# tuch-tara2.net
KiCad netlist of a schematic drawn in Altium Designer
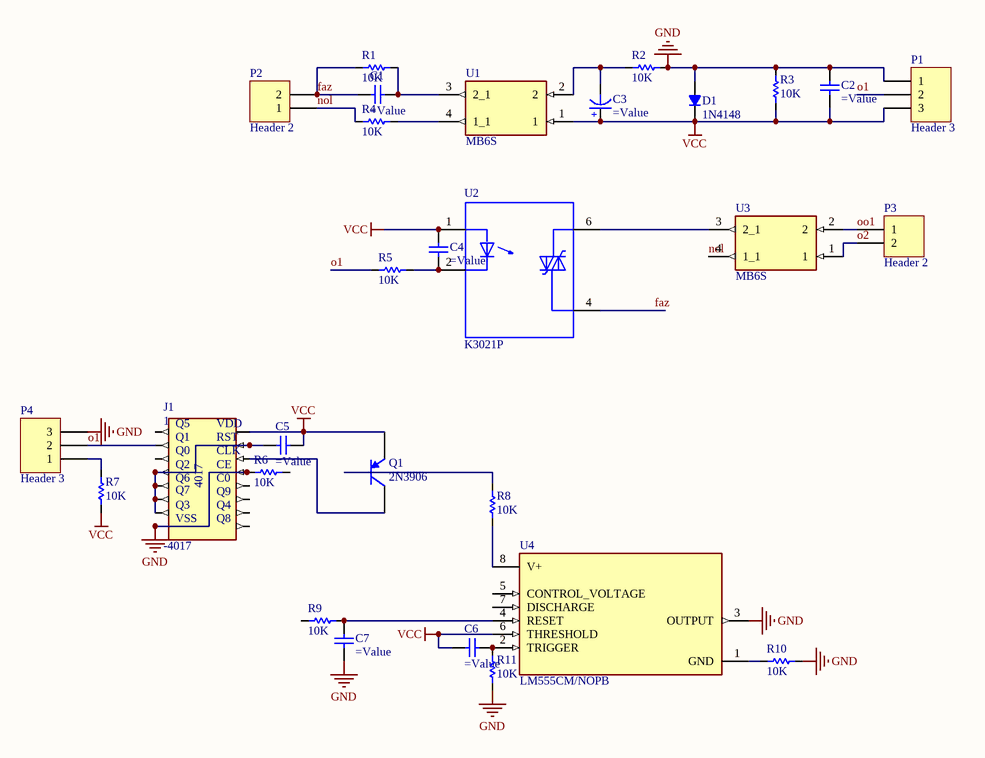
[diagram p0: tuch-tara2.SchDoc]

(export (version "E")
  (design (tool "Eeschema 10.0.6"))
  (components
    (comp (ref "C1")
      (value "~")
      (footprint "CAP-30")
      (description "Capacitor")
      (libsource (lib "AltiumLib1") (part "Capacitor"))
    )
    (comp (ref "C2")
      (value "~")
      (footprint "CAP 1206")
      (description "Capacitor")
      (libsource (lib "AltiumLib1") (part "Capacitor"))
    )
    (comp (ref "C3")
      (value "~")
      (footprint "ELEC-CAP-RAD10-20")
      (description "Electrolytic Capacitor")
      (libsource (lib "AltiumLib1") (part "Capacitor Electrolytic"))
    )
    (comp (ref "C4")
      (value "~")
      (footprint "CAP 1206")
      (description "Capacitor")
      (libsource (lib "AltiumLib1") (part "Capacitor"))
    )
    (comp (ref "C5")
      (value "~")
      (footprint "CAP 1206")
      (description "Capacitor")
      (libsource (lib "AltiumLib1") (part "Capacitor"))
    )
    (comp (ref "C6")
      (value "~")
      (footprint "CAP 1206")
      (description "Capacitor")
      (libsource (lib "AltiumLib1") (part "Capacitor"))
    )
    (comp (ref "C7")
      (value "~")
      (footprint "CAP 1206")
      (description "Capacitor")
      (libsource (lib "AltiumLib1") (part "Capacitor"))
    )
    (comp (ref "D1")
      (value "MODEL")
      (footprint "DO-41")
      (description "Diode")
      (fields (field (name "MODEL") "1N4148"))
      (libsource (lib "AltiumLib1") (part "Diode"))
    )
    (comp (ref "J1")
      (value "-4017")
      (footprint "SOIC127P600X175-16N")
      (description "10000pF Â±1% 25V Ceramic Capacitor C0G, NP0 0603 (1608 Metric)")
      (fields (field (name "MF") "Heyco") (field (name "MP") "4017"))
      (libsource (lib "-4017") (part "-4017"))
    )
    (comp (ref "P1")
      (value "Header 3")
      (footprint "HDR1X3")
      (description "Header, 3-Pin")
      (fields (field (name "PUBLISHER") "Altium Limited"))
      (libsource (lib "") (part "Header 3_1"))
    )
    (comp (ref "P2")
      (value "Header 2")
      (footprint "HDR1X2")
      (description "Header, 2-Pin")
      (fields (field (name "PUBLISHER") "Altium Limited"))
      (libsource (lib "") (part "Header 2_1"))
    )
    (comp (ref "P3")
      (value "Header 2")
      (footprint "HDR1X2")
      (description "Header, 2-Pin")
      (fields (field (name "PUBLISHER") "Altium Limited"))
      (libsource (lib "Miscellaneous Connectors") (part "Header 2"))
    )
    (comp (ref "P4")
      (value "Header 3")
      (footprint "HDR1X3")
      (description "Header, 3-Pin")
      (fields (field (name "PUBLISHER") "Altium Limited"))
      (libsource (lib "Miscellaneous Connectors") (part "Header 3"))
    )
    (comp (ref "Q1")
      (value "2N3906")
      (footprint "MMBT3904-TP:SOT23-3")
      (description "PNP General Purpose Amplifier")
      (fields (field (name "PUBLISHER") "Altium Limited"))
      (libsource (lib "Miscellaneous Devices") (part "2N3906"))
    )
    (comp (ref "R1")
      (value "10K")
      (footprint "RES 1206 (3216X08L)")
      (description "Resistor")
      (fields (field (name "TOLERANCE") "5%") (field (name "POWER") "1/4 W"))
      (libsource (lib "AltiumLib1") (part "Resistor"))
    )
    (comp (ref "R2")
      (value "10K")
      (footprint "RES 1206 (3216X08L)")
      (description "Resistor")
      (fields (field (name "TOLERANCE") "5%") (field (name "POWER") "1/4 W"))
      (libsource (lib "AltiumLib1") (part "Resistor"))
    )
    (comp (ref "R3")
      (value "10K")
      (footprint "RES 1206 (3216X08L)")
      (description "Resistor")
      (fields (field (name "TOLERANCE") "5%") (field (name "POWER") "1/4 W"))
      (libsource (lib "AltiumLib1") (part "Resistor"))
    )
    (comp (ref "R4")
      (value "10K")
      (footprint "RES 2512 (6331X07L)")
      (description "Resistor")
      (fields (field (name "TOLERANCE") "5%") (field (name "POWER") "1/4 W"))
      (libsource (lib "AltiumLib1") (part "Resistor"))
    )
    (comp (ref "R5")
      (value "10K")
      (footprint "RES 1206 (3216X08L)")
      (description "Resistor")
      (fields (field (name "TOLERANCE") "5%") (field (name "POWER") "1/4 W"))
      (libsource (lib "AltiumLib1") (part "Resistor"))
    )
    (comp (ref "R6")
      (value "10K")
      (footprint "RES 1206 (3216X08L)")
      (description "Resistor")
      (fields (field (name "TOLERANCE") "5%") (field (name "POWER") "1/4 W"))
      (libsource (lib "AltiumLib1") (part "Resistor"))
    )
    (comp (ref "R7")
      (value "10K")
      (footprint "Res-(1/4)")
      (description "Resistor")
      (fields (field (name "TOLERANCE") "5%") (field (name "POWER") "1/4 W"))
      (libsource (lib "AltiumLib1") (part "Resistor"))
    )
    (comp (ref "R8")
      (value "10K")
      (footprint "RES 1206 (3216X08L)")
      (description "Resistor")
      (fields (field (name "TOLERANCE") "5%") (field (name "POWER") "1/4 W"))
      (libsource (lib "AltiumLib1") (part "Resistor"))
    )
    (comp (ref "R9")
      (value "10K")
      (footprint "RES 1206 (3216X08L)")
      (description "Resistor")
      (fields (field (name "TOLERANCE") "5%") (field (name "POWER") "1/4 W"))
      (libsource (lib "AltiumLib1") (part "Resistor"))
    )
    (comp (ref "R10")
      (value "10K")
      (footprint "RES 1206 (3216X08L)")
      (description "Resistor")
      (fields (field (name "TOLERANCE") "5%") (field (name "POWER") "1/4 W"))
      (libsource (lib "AltiumLib1") (part "Resistor"))
    )
    (comp (ref "R11")
      (value "10K")
      (footprint "RES 1206 (3216X08L)")
      (description "Resistor")
      (fields (field (name "TOLERANCE") "5%") (field (name "POWER") "1/4 W"))
      (libsource (lib "AltiumLib1") (part "Resistor"))
    )
    (comp (ref "U1")
      (value "MB6S")
      (footprint "SOIC245P670X270-4N")
      (description "Bridge Rectifier Single Phase Standard 600V Surface Mount 4-SOIC")
      (fields (field (name "MF") "ON Semiconductor") (field (name "DIGI-KEY_PART_NUMBER") "MB6SCT-ND"))
      (libsource (lib "MB6S") (part "MB6S"))
    )
    (comp (ref "U2")
      (value "K3021P")
      (footprint "DIP762W50P254L730H410Q6")
      (description "Optoisolator Triac Output 5300Vrms 1 Channel 6-DIP")
      (fields (field (name "MF") "Vishay Semiconductor"))
      (libsource (lib "K3021P") (part "K3021P"))
    )
    (comp (ref "U3")
      (value "MB6S")
      (footprint "SOIC245P670X270-4N")
      (description "Bridge Rectifier Single Phase Standard 600V Surface Mount 4-SOIC")
      (fields (field (name "MF") "ON Semiconductor") (field (name "DIGI-KEY_PART_NUMBER") "MB6SCT-ND"))
      (libsource (lib "MB6S") (part "MB6S"))
    )
    (comp (ref "U4")
      (value "LM555CM/NOPB")
      (footprint "SOIC127P599X175-8N")
      (description "Highly Stable 555 Timer 8-SOIC 0 to 70")
      (libsource (lib "LM555CM_NOPB") (part "LM555CM/NOPB"))
    )
  )
  (nets
    (net (code "1") (name "/faz") (class "Default")
      (node (ref "C1") (pin "1") (pinfunction "+_1") (pintype "passive"))
      (node (ref "P2") (pin "2") (pinfunction "2_2") (pintype "passive"))
      (node (ref "R1") (pin "2") (pinfunction "2_2") (pintype "passive"))
      (node (ref "U2") (pin "4") (pinfunction "MT1_4") (pintype "passive"))
    )
    (net (code "2") (name "/nol") (class "Default")
      (node (ref "P2") (pin "1") (pinfunction "1_1") (pintype "passive"))
      (node (ref "R4") (pin "2") (pinfunction "2_2") (pintype "passive"))
      (node (ref "U3") (pin "4") (pinfunction "1_1_4") (pintype "output"))
    )
    (net (code "3") (name "/o1") (class "Default")
      (node (ref "J1") (pin "2") (pinfunction "Q1_2") (pintype "output"))
      (node (ref "P1") (pin "2") (pinfunction "2_2") (pintype "passive"))
      (node (ref "P4") (pin "2") (pinfunction "2_2") (pintype "passive"))
      (node (ref "R5") (pin "1") (pinfunction "1_1") (pintype "passive"))
    )
    (net (code "4") (name "/o2") (class "Default")
      (node (ref "P3") (pin "2") (pinfunction "2_2") (pintype "passive"))
      (node (ref "U3") (pin "1") (pinfunction "1_1") (pintype "input"))
    )
    (net (code "5") (name "/oo1") (class "Default")
      (node (ref "P3") (pin "1") (pinfunction "1_1") (pintype "passive"))
      (node (ref "U3") (pin "2") (pinfunction "2_2") (pintype "input"))
    )
    (net (code "6") (name "GND") (class "Default")
      (node (ref "C2") (pin "2") (pinfunction "-_2") (pintype "passive"))
      (node (ref "C7") (pin "2") (pinfunction "-_2") (pintype "passive"))
      (node (ref "D1") (pin "1") (pinfunction "A_1") (pintype "passive"))
      (node (ref "J1") (pin "13") (pinfunction "CE_13") (pintype "input"))
      (node (ref "J1") (pin "8") (pinfunction "VSS_8") (pintype "power_in"))
      (node (ref "P1") (pin "1") (pinfunction "1_1") (pintype "passive"))
      (node (ref "P4") (pin "3") (pinfunction "3_3") (pintype "passive"))
      (node (ref "R10") (pin "2") (pinfunction "2_2") (pintype "passive"))
      (node (ref "R11") (pin "1") (pinfunction "1_1") (pintype "passive"))
      (node (ref "R2") (pin "2") (pinfunction "2_2") (pintype "passive"))
      (node (ref "R3") (pin "2") (pinfunction "2_2") (pintype "passive"))
      (node (ref "R6") (pin "1") (pinfunction "1_1") (pintype "passive"))
      (node (ref "U4") (pin "3") (pinfunction "OUTPUT_3") (pintype "output"))
    )
    (net (code "7") (name "Net-(C1--)") (class "Default")
      (node (ref "C1") (pin "2") (pinfunction "-_2") (pintype "passive"))
      (node (ref "R1") (pin "1") (pinfunction "1_1") (pintype "passive"))
      (node (ref "U1") (pin "3") (pinfunction "2_1_3") (pintype "output"))
    )
    (net (code "8") (name "Net-(C3--)") (class "Default")
      (node (ref "C3") (pin "1") (pinfunction "-_1") (pintype "passive"))
      (node (ref "R2") (pin "1") (pinfunction "1_1") (pintype "passive"))
      (node (ref "U1") (pin "2") (pinfunction "2_2") (pintype "input"))
    )
    (net (code "9") (name "Net-(C4-+)") (class "Default")
      (node (ref "C4") (pin "1") (pinfunction "+_1") (pintype "passive"))
      (node (ref "R5") (pin "2") (pinfunction "2_2") (pintype "passive"))
      (node (ref "U2") (pin "2") (pinfunction "C_2") (pintype "passive"))
    )
    (net (code "10") (name "Net-(C5--)") (class "Default")
      (node (ref "C5") (pin "2") (pinfunction "-_2") (pintype "passive"))
      (node (ref "J1") (pin "15") (pinfunction "RST_15") (pintype "input"))
      (node (ref "J1") (pin "4") (pinfunction "Q2_4") (pintype "output"))
      (node (ref "J1") (pin "5") (pinfunction "Q6_5") (pintype "output"))
      (node (ref "J1") (pin "6") (pinfunction "Q7_6") (pintype "output"))
      (node (ref "J1") (pin "7") (pinfunction "Q3_7") (pintype "output"))
    )
    (net (code "11") (name "Net-(C6-+)") (class "Default")
      (node (ref "C6") (pin "1") (pinfunction "+_1") (pintype "passive"))
      (node (ref "R11") (pin "2") (pinfunction "2_2") (pintype "passive"))
      (node (ref "U4") (pin "2") (pinfunction "TRIGGER_2") (pintype "input"))
    )
    (net (code "12") (name "Net-(C7-+)") (class "Default")
      (node (ref "C7") (pin "1") (pinfunction "+_1") (pintype "passive"))
      (node (ref "R9") (pin "2") (pinfunction "2_2") (pintype "passive"))
      (node (ref "U4") (pin "4") (pinfunction "RESET_4") (pintype "input"))
    )
    (net (code "13") (name "Net-(J1-CLK)") (class "Default")
      (node (ref "J1") (pin "14") (pinfunction "CLK_14") (pintype "input"))
      (node (ref "Q1") (pin "3") (pinfunction "C_3") (pintype "passive"))
    )
    (net (code "14") (name "Net-(P4-Pad1)") (class "Default")
      (node (ref "P4") (pin "1") (pinfunction "1_1") (pintype "passive"))
      (node (ref "R7") (pin "2") (pinfunction "2_2") (pintype "passive"))
    )
    (net (code "15") (name "Net-(Q1-B)") (class "Default")
      (node (ref "Q1") (pin "2") (pinfunction "B_2") (pintype "passive"))
      (node (ref "R8") (pin "2") (pinfunction "2_2") (pintype "passive"))
    )
    (net (code "16") (name "Net-(U1-1_1)") (class "Default")
      (node (ref "R4") (pin "1") (pinfunction "1_1") (pintype "passive"))
      (node (ref "U1") (pin "4") (pinfunction "1_1_4") (pintype "output"))
    )
    (net (code "17") (name "Net-(U2-MT2)") (class "Default")
      (node (ref "U2") (pin "6") (pinfunction "MT2_6") (pintype "passive"))
      (node (ref "U3") (pin "3") (pinfunction "2_1_3") (pintype "output"))
    )
    (net (code "18") (name "Net-(U4-GND)") (class "Default")
      (node (ref "R10") (pin "1") (pinfunction "1_1") (pintype "passive"))
      (node (ref "U4") (pin "1") (pinfunction "GND_1") (pintype "power_in"))
    )
    (net (code "19") (name "Net-(U4-V+)") (class "Default")
      (node (ref "R8") (pin "1") (pinfunction "1_1") (pintype "passive"))
      (node (ref "U4") (pin "8") (pinfunction "V+_8") (pintype "power_in"))
    )
    (net (code "20") (name "VCC") (class "Default")
      (node (ref "C2") (pin "1") (pinfunction "+_1") (pintype "passive"))
      (node (ref "C3") (pin "2") (pinfunction "+_2") (pintype "passive"))
      (node (ref "C4") (pin "2") (pinfunction "-_2") (pintype "passive"))
      (node (ref "C5") (pin "1") (pinfunction "+_1") (pintype "passive"))
      (node (ref "C6") (pin "2") (pinfunction "-_2") (pintype "passive"))
      (node (ref "D1") (pin "2") (pinfunction "K_2") (pintype "passive"))
      (node (ref "J1") (pin "16") (pinfunction "VDD_16") (pintype "power_in"))
      (node (ref "P1") (pin "3") (pinfunction "3_3") (pintype "passive"))
      (node (ref "Q1") (pin "1") (pinfunction "E_1") (pintype "passive"))
      (node (ref "R3") (pin "1") (pinfunction "1_1") (pintype "passive"))
      (node (ref "R7") (pin "1") (pinfunction "1_1") (pintype "passive"))
      (node (ref "U1") (pin "1") (pinfunction "1_1") (pintype "input"))
      (node (ref "U2") (pin "1") (pinfunction "A_1") (pintype "passive"))
      (node (ref "U4") (pin "6") (pinfunction "THRESHOLD_6") (pintype "input"))
    )
    (net (code "21") (name "unconnected-(J1-C0-Pad12)") (class "Default")
      (node (ref "J1") (pin "12") (pinfunction "C0_12") (pintype "output"))
    )
    (net (code "22") (name "unconnected-(J1-Q0-Pad3)") (class "Default")
      (node (ref "J1") (pin "3") (pinfunction "Q0_3") (pintype "output"))
    )
    (net (code "23") (name "unconnected-(J1-Q4-Pad10)") (class "Default")
      (node (ref "J1") (pin "10") (pinfunction "Q4_10") (pintype "output"))
    )
    (net (code "24") (name "unconnected-(J1-Q5-Pad1)") (class "Default")
      (node (ref "J1") (pin "1") (pinfunction "Q5_1") (pintype "output"))
    )
    (net (code "25") (name "unconnected-(J1-Q8-Pad9)") (class "Default")
      (node (ref "J1") (pin "9") (pinfunction "Q8_9") (pintype "output"))
    )
    (net (code "26") (name "unconnected-(J1-Q9-Pad11)") (class "Default")
      (node (ref "J1") (pin "11") (pinfunction "Q9_11") (pintype "output"))
    )
    (net (code "27") (name "unconnected-(R6-Pad2)") (class "Default")
      (node (ref "R6") (pin "2") (pinfunction "2_2") (pintype "passive"))
    )
    (net (code "28") (name "unconnected-(R9-Pad1)") (class "Default")
      (node (ref "R9") (pin "1") (pinfunction "1_1") (pintype "passive"))
    )
    (net (code "29") (name "unconnected-(U4-CONTROL_VOLTAGE-Pad5)") (class "Default")
      (node (ref "U4") (pin "5") (pinfunction "CONTROL_VOLTAGE_5") (pintype "input"))
    )
    (net (code "30") (name "unconnected-(U4-DISCHARGE-Pad7)") (class "Default")
      (node (ref "U4") (pin "7") (pinfunction "DISCHARGE_7") (pintype "input"))
    )
  )
)
